# Shield_DMM.net
KiCad netlist of a schematic drawn in EAGLE
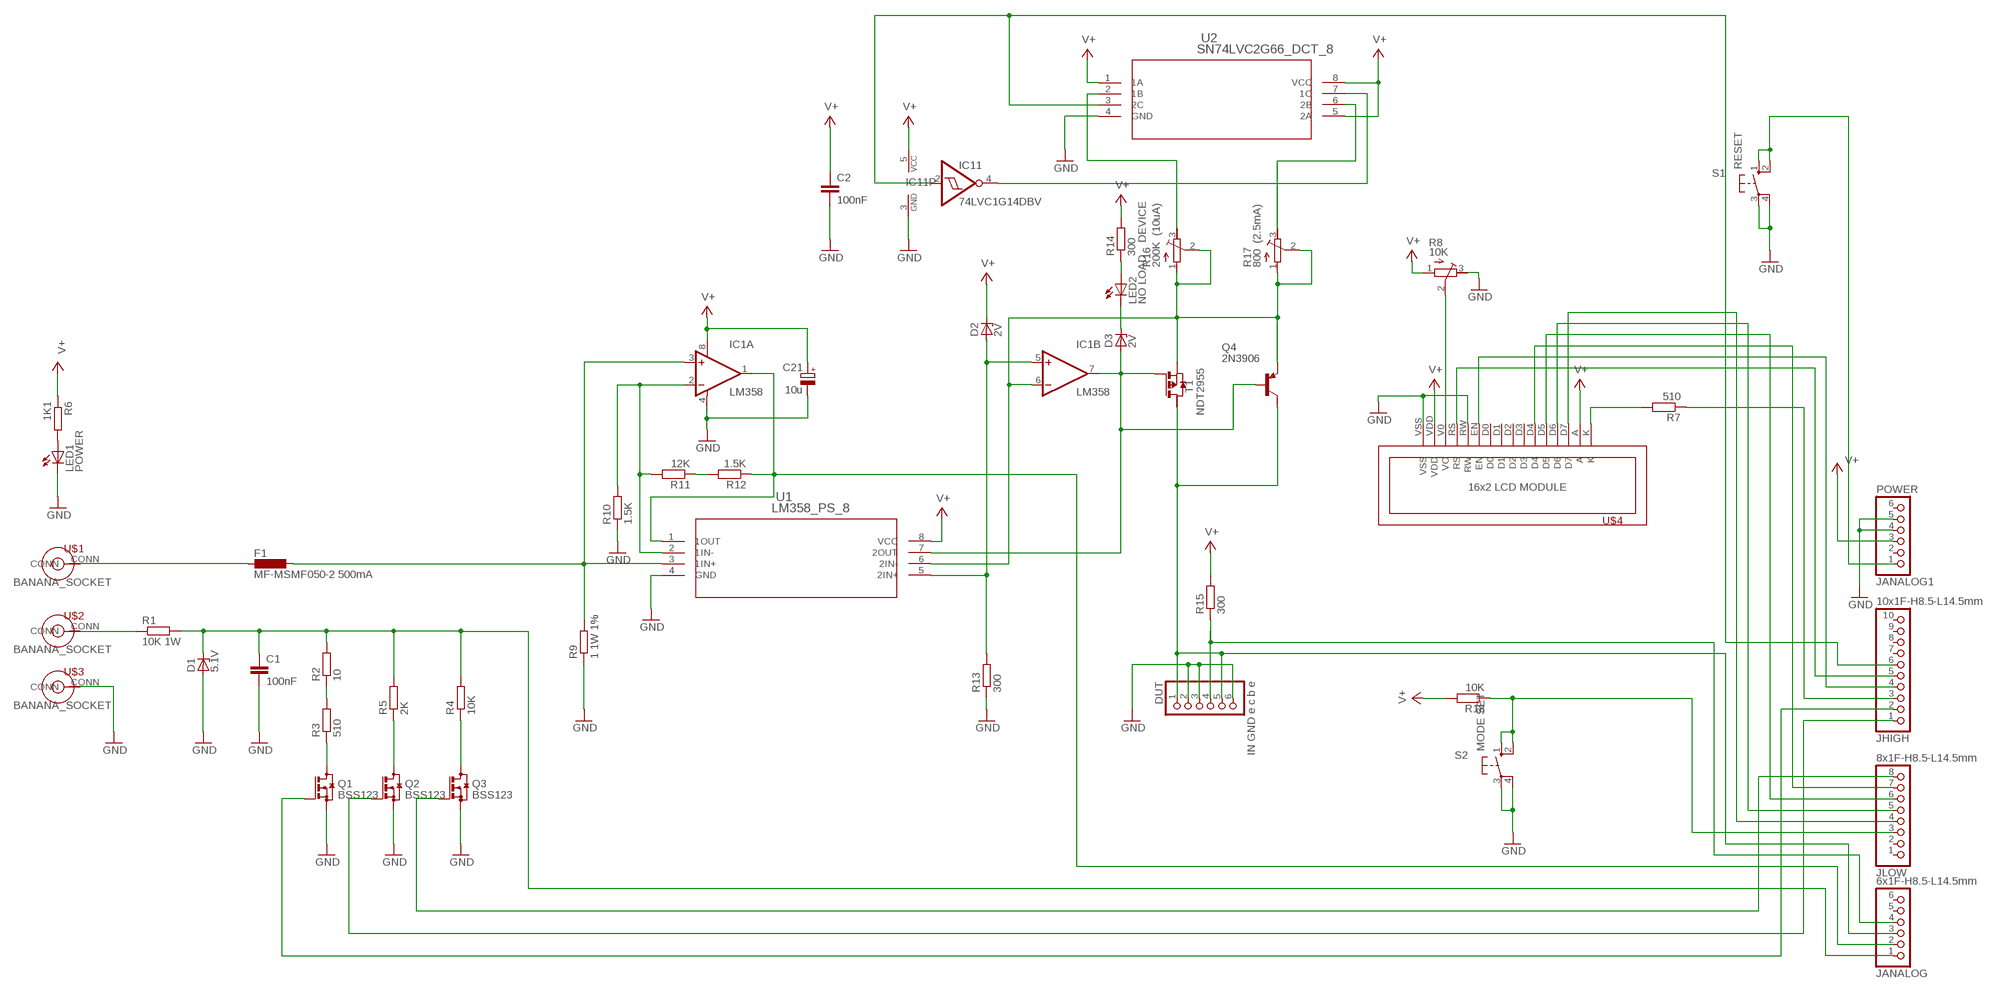
[diagram p0: schematic, sheet 1]

(export (version "E")
  (design (tool "Eeschema 10.0.6"))
  (components
    (comp (ref "C1")
      (value "100nF")
      (footprint "eagle-import:C0805")
      (libsource (lib "eagle-import") (part "C-EUC0805"))
    )
    (comp (ref "C2")
      (value "100nF")
      (footprint "eagle-import:C0805")
      (libsource (lib "eagle-import") (part "C-EUC0805"))
    )
    (comp (ref "C21")
      (value "10u")
      (footprint "eagle-import:085CS_1AR")
      (libsource (lib "eagle-import") (part "CPOL-EU085CS-1AR"))
    )
    (comp (ref "D1")
      (value "5.1V")
      (footprint "eagle-import:DO34Z7")
      (libsource (lib "eagle-import") (part "BZV10"))
    )
    (comp (ref "D2")
      (value "2V")
      (footprint "eagle-import:DO34Z7")
      (libsource (lib "eagle-import") (part "BZV10"))
    )
    (comp (ref "D3")
      (value "2V")
      (footprint "eagle-import:DO34Z7")
      (libsource (lib "eagle-import") (part "BZV10"))
    )
    (comp (ref "DUT")
      (value "IN GND e c b e")
      (footprint "eagle-import:1X06")
      (libsource (lib "eagle-import") (part "PINHD-1X6"))
    )
    (comp (ref "F1")
      (value "MF-MSMF050-2 500mA")
      (footprint "eagle-import:L1812")
      (libsource (lib "eagle-import") (part "L-EUL1812"))
    )
    (comp (ref "IC1")
      (value "LM358")
      (footprint "eagle-import:SO08")
      (fields (field (name "MF") "TEXAS INSTRUMENTS") (field (name "MPN") "OPA2340UA"))
      (libsource (lib "eagle-import") (part "OPA2340U"))
    )
    (comp (ref "IC11")
      (value "74LVC1G14DBV")
      (footprint "eagle-import:SOT23-5")
      (libsource (lib "eagle-import") (part "741G14DBVLVC"))
    )
    (comp (ref "JANALOG")
      (value "6x1F-H8.5-L14.5mm")
      (footprint "eagle-import:1X06")
      (libsource (lib "eagle-import") (part "PINHD-1X6"))
    )
    (comp (ref "JANALOG1")
      (value "POWER")
      (footprint "eagle-import:1X06")
      (libsource (lib "eagle-import") (part "PINHD-1X6"))
    )
    (comp (ref "JHIGH")
      (value "10x1F-H8.5-L14.5mm")
      (footprint "eagle-import:1X10")
      (libsource (lib "eagle-import") (part "PINHD-1X10"))
    )
    (comp (ref "JLOW")
      (value "8x1F-H8.5-L14.5mm")
      (footprint "eagle-import:1X08")
      (libsource (lib "eagle-import") (part "PINHD-1X8"))
    )
    (comp (ref "LED1")
      (value "POWER")
      (footprint "eagle-import:CHIPLED_0805")
      (libsource (lib "eagle-import") (part "LEDCHIPLED_0805"))
    )
    (comp (ref "LED2")
      (value "NO LOAD DEVICE")
      (footprint "eagle-import:CHIPLED_0805")
      (libsource (lib "eagle-import") (part "LEDCHIPLED_0805"))
    )
    (comp (ref "Q1")
      (value "BSS123")
      (footprint "eagle-import:SOT23")
      (libsource (lib "eagle-import") (part "BSS123"))
    )
    (comp (ref "Q2")
      (value "BSS123")
      (footprint "eagle-import:SOT23")
      (libsource (lib "eagle-import") (part "BSS123"))
    )
    (comp (ref "Q3")
      (value "BSS123")
      (footprint "eagle-import:SOT23")
      (libsource (lib "eagle-import") (part "BSS123"))
    )
    (comp (ref "Q4")
      (value "2N3906")
      (footprint "eagle-import:TO92")
      (libsource (lib "eagle-import") (part "2N3906"))
    )
    (comp (ref "R1")
      (value "10K 1W")
      (footprint "eagle-import:0207_10")
      (libsource (lib "eagle-import") (part "R-EU_0207/10"))
    )
    (comp (ref "R2")
      (value "10")
      (footprint "eagle-import:R0805")
      (libsource (lib "eagle-import") (part "R-EU_R0805"))
    )
    (comp (ref "R3")
      (value "510")
      (footprint "eagle-import:R0805")
      (libsource (lib "eagle-import") (part "R-EU_R0805"))
    )
    (comp (ref "R4")
      (value "10K")
      (footprint "eagle-import:R0805")
      (libsource (lib "eagle-import") (part "R-EU_R0805"))
    )
    (comp (ref "R5")
      (value "2K")
      (footprint "eagle-import:R0805")
      (libsource (lib "eagle-import") (part "R-EU_R0805"))
    )
    (comp (ref "R6")
      (value "1K1")
      (footprint "eagle-import:R0805")
      (libsource (lib "eagle-import") (part "R-EU_R0805"))
    )
    (comp (ref "R7")
      (value "510")
      (footprint "eagle-import:R0805")
      (libsource (lib "eagle-import") (part "R-EU_R0805"))
    )
    (comp (ref "R8")
      (value "10K")
      (footprint "eagle-import:RTRIM64W")
      (libsource (lib "eagle-import") (part "R-TRIMM64W"))
    )
    (comp (ref "R9")
      (value "1 1W 1%")
      (footprint "eagle-import:0207_10")
      (libsource (lib "eagle-import") (part "R-EU_0207/10"))
    )
    (comp (ref "R10")
      (value "1.5K")
      (footprint "eagle-import:R0805")
      (libsource (lib "eagle-import") (part "R-EU_R0805"))
    )
    (comp (ref "R11")
      (value "12K")
      (footprint "eagle-import:R0805")
      (libsource (lib "eagle-import") (part "R-EU_R0805"))
    )
    (comp (ref "R12")
      (value "1.5K")
      (footprint "eagle-import:R0805")
      (libsource (lib "eagle-import") (part "R-EU_R0805"))
    )
    (comp (ref "R13")
      (value "300")
      (footprint "eagle-import:R0805")
      (libsource (lib "eagle-import") (part "R-EU_R0805"))
    )
    (comp (ref "R14")
      (value "300")
      (footprint "eagle-import:R0805")
      (libsource (lib "eagle-import") (part "R-EU_R0805"))
    )
    (comp (ref "R15")
      (value "300")
      (footprint "eagle-import:R0805")
      (libsource (lib "eagle-import") (part "R-EU_R0805"))
    )
    (comp (ref "R16")
      (value "200K (10uA)")
      (footprint "eagle-import:RTRIM64W")
      (libsource (lib "eagle-import") (part "R-TRIMM64W"))
    )
    (comp (ref "R17")
      (value "800 (2.5mA)")
      (footprint "eagle-import:RTRIM64W")
      (libsource (lib "eagle-import") (part "R-TRIMM64W"))
    )
    (comp (ref "R18")
      (value "10K")
      (footprint "eagle-import:R0805")
      (libsource (lib "eagle-import") (part "R-EU_R0805"))
    )
    (comp (ref "S1")
      (value "RESET")
      (footprint "eagle-import:B3F-10XX")
      (libsource (lib "eagle-import") (part "10-XX"))
    )
    (comp (ref "S2")
      (value "MODE SET")
      (footprint "eagle-import:B3F-10XX")
      (libsource (lib "eagle-import") (part "10-XX"))
    )
    (comp (ref "T1")
      (value "NDT2955")
      (footprint "eagle-import:SOT223")
      (libsource (lib "eagle-import") (part "PMOSSOT223"))
    )
    (comp (ref "U$1")
      (value "BANANA_CONN")
      (footprint "eagle-import:BANANA_CONN")
      (libsource (lib "eagle-import") (part "BANANA_CONN"))
    )
    (comp (ref "U$2")
      (value "BANANA_CONN")
      (footprint "eagle-import:BANANA_CONN")
      (libsource (lib "eagle-import") (part "BANANA_CONN"))
    )
    (comp (ref "U$3")
      (value "BANANA_CONN")
      (footprint "eagle-import:BANANA_CONN")
      (libsource (lib "eagle-import") (part "BANANA_CONN"))
    )
    (comp (ref "U$4")
      (value "1602_LCM")
      (footprint "eagle-import:1602_LCM")
      (libsource (lib "eagle-import") (part "1602_LCM"))
    )
    (comp (ref "U1")
      (value "LM358_PS_8")
      (footprint "eagle-import:PS8")
      (fields (field (name "GENERIC_PART_NUMBER") "LM358") (field (name "MANUFACTURER") "Texas Instruments"))
      (libsource (lib "eagle-import") (part "LM358_PS_8"))
    )
    (comp (ref "U2")
      (value "SN74LVC2G66_DCT_8")
      (footprint "eagle-import:DCT8")
      (fields
        (field (name "GENERIC_PART_NUMBER") "SN74LVC2G66")
        (field (name "MANUFACTURER") "Texas Instruments")
        (field (name "MANUFACTURER_PART_NUMBER") "sn74lvc2g66_dct_8")
      )
      (libsource (lib "eagle-import") (part "SN74LVC2G66_DCT_8"))
    )
  )
  (nets
    (net (code "1") (name "GND") (class "Default")
      (node (ref "C1") (pin "2") (pinfunction "2_2") (pintype "passive"))
      (node (ref "C2") (pin "2") (pinfunction "2_2") (pintype "passive"))
      (node (ref "C21") (pin "-") (pinfunction "-_-") (pintype "passive"))
      (node (ref "D1") (pin "A") (pinfunction "A_A") (pintype "passive"))
      (node (ref "DUT") (pin "2") (pinfunction "2_2") (pintype "passive"))
      (node (ref "DUT") (pin "3") (pinfunction "3_3") (pintype "passive"))
      (node (ref "DUT") (pin "6") (pinfunction "6_6") (pintype "passive"))
      (node (ref "IC1") (pin "4") (pinfunction "V-_4") (pintype "power_in"))
      (node (ref "IC11") (pin "3") (pinfunction "GND_3") (pintype "power_in"))
      (node (ref "JANALOG1") (pin "4") (pinfunction "4_4") (pintype "passive"))
      (node (ref "JANALOG1") (pin "5") (pinfunction "5_5") (pintype "passive"))
      (node (ref "LED1") (pin "C") (pinfunction "C_C") (pintype "passive"))
      (node (ref "Q1") (pin "2") (pinfunction "S_2") (pintype "passive"))
      (node (ref "Q2") (pin "2") (pinfunction "S_2") (pintype "passive"))
      (node (ref "Q3") (pin "2") (pinfunction "S_2") (pintype "passive"))
      (node (ref "R10") (pin "1") (pinfunction "1_1") (pintype "passive"))
      (node (ref "R13") (pin "1") (pinfunction "1_1") (pintype "passive"))
      (node (ref "R8") (pin "3") (pinfunction "E_3") (pintype "passive"))
      (node (ref "R9") (pin "1") (pinfunction "1_1") (pintype "passive"))
      (node (ref "S1") (pin "3") (pinfunction "P_3") (pintype "passive"))
      (node (ref "S1") (pin "4") (pinfunction "P1_4") (pintype "passive"))
      (node (ref "S2") (pin "3") (pinfunction "P_3") (pintype "passive"))
      (node (ref "S2") (pin "4") (pinfunction "P1_4") (pintype "passive"))
      (node (ref "U$3") (pin "CONN") (pinfunction "CONN_CONN") (pintype "bidirectional"))
      (node (ref "U$4") (pin "RW") (pinfunction "RW_RW") (pintype "bidirectional"))
      (node (ref "U$4") (pin "VSS") (pinfunction "VSS_VSS") (pintype "bidirectional"))
      (node (ref "U1") (pin "4") (pinfunction "GND_4") (pintype "power_in"))
      (node (ref "U2") (pin "4") (pinfunction "GND_4") (pintype "power_in"))
    )
    (net (code "2") (name "Net-(C1-Pad1)") (class "Default")
      (node (ref "C1") (pin "1") (pinfunction "1_1") (pintype "passive"))
      (node (ref "D1") (pin "C") (pinfunction "C_C") (pintype "passive"))
      (node (ref "JANALOG") (pin "1") (pinfunction "1_1") (pintype "passive"))
      (node (ref "R1") (pin "2") (pinfunction "2_2") (pintype "passive"))
      (node (ref "R2") (pin "2") (pinfunction "2_2") (pintype "passive"))
      (node (ref "R4") (pin "2") (pinfunction "2_2") (pintype "passive"))
      (node (ref "R5") (pin "2") (pinfunction "2_2") (pintype "passive"))
    )
    (net (code "3") (name "Net-(D3-PadC)") (class "Default")
      (node (ref "D3") (pin "C") (pinfunction "C_C") (pintype "passive"))
      (node (ref "LED2") (pin "C") (pinfunction "C_C") (pintype "passive"))
    )
    (net (code "4") (name "Net-(DUT-Pad4)") (class "Default")
      (node (ref "DUT") (pin "4") (pinfunction "4_4") (pintype "passive"))
      (node (ref "JANALOG") (pin "4") (pinfunction "4_4") (pintype "passive"))
      (node (ref "R15") (pin "1") (pinfunction "1_1") (pintype "passive"))
    )
    (net (code "5") (name "Net-(F1-Pad2)") (class "Default")
      (node (ref "F1") (pin "2") (pinfunction "2_2") (pintype "passive"))
      (node (ref "U$1") (pin "CONN") (pinfunction "CONN_CONN") (pintype "bidirectional"))
    )
    (net (code "6") (name "Net-(IC1A-+IN)") (class "Default")
      (node (ref "F1") (pin "1") (pinfunction "1_1") (pintype "passive"))
      (node (ref "IC1") (pin "3") (pinfunction "+IN_3") (pintype "input"))
      (node (ref "R9") (pin "2") (pinfunction "2_2") (pintype "passive"))
      (node (ref "U1") (pin "3") (pinfunction "1IN+_3") (pintype "input"))
    )
    (net (code "7") (name "Net-(IC1A--IN)") (class "Default")
      (node (ref "IC1") (pin "2") (pinfunction "-IN_2") (pintype "input"))
      (node (ref "R10") (pin "2") (pinfunction "2_2") (pintype "passive"))
      (node (ref "R11") (pin "2") (pinfunction "2_2") (pintype "passive"))
      (node (ref "U1") (pin "2") (pinfunction "1IN-_2") (pintype "input"))
    )
    (net (code "8") (name "Net-(IC1A-OUT)") (class "Default")
      (node (ref "IC1") (pin "1") (pinfunction "OUT_1") (pintype "output"))
      (node (ref "JANALOG") (pin "2") (pinfunction "2_2") (pintype "passive"))
      (node (ref "R12") (pin "1") (pinfunction "1_1") (pintype "passive"))
      (node (ref "U1") (pin "1") (pinfunction "1OUT_1") (pintype "output"))
    )
    (net (code "9") (name "Net-(IC1B-+IN)") (class "Default")
      (node (ref "D2") (pin "A") (pinfunction "A_A") (pintype "passive"))
      (node (ref "IC1") (pin "5") (pinfunction "+IN_5") (pintype "input"))
      (node (ref "R13") (pin "2") (pinfunction "2_2") (pintype "passive"))
      (node (ref "U1") (pin "5") (pinfunction "2IN+_5") (pintype "input"))
    )
    (net (code "10") (name "Net-(IC1B--IN)") (class "Default")
      (node (ref "IC1") (pin "6") (pinfunction "-IN_6") (pintype "input"))
      (node (ref "Q4") (pin "3") (pinfunction "E_3") (pintype "passive"))
      (node (ref "R16") (pin "1") (pinfunction "A_1") (pintype "passive"))
      (node (ref "R16") (pin "2") (pinfunction "S_2") (pintype "passive"))
      (node (ref "R17") (pin "1") (pinfunction "A_1") (pintype "passive"))
      (node (ref "R17") (pin "2") (pinfunction "S_2") (pintype "passive"))
      (node (ref "T1") (pin "3") (pinfunction "S_3") (pintype "passive"))
      (node (ref "U1") (pin "6") (pinfunction "2IN-_6") (pintype "input"))
    )
    (net (code "11") (name "Net-(IC1B-OUT)") (class "Default")
      (node (ref "D3") (pin "A") (pinfunction "A_A") (pintype "passive"))
      (node (ref "IC1") (pin "7") (pinfunction "OUT_7") (pintype "output"))
      (node (ref "Q4") (pin "2") (pinfunction "B_2") (pintype "passive"))
      (node (ref "T1") (pin "1") (pinfunction "G_1") (pintype "passive"))
      (node (ref "U1") (pin "7") (pinfunction "2OUT_7") (pintype "output"))
    )
    (net (code "12") (name "Net-(IC11A-I)") (class "Default")
      (node (ref "IC11") (pin "2") (pinfunction "I_2") (pintype "input"))
      (node (ref "JHIGH") (pin "6") (pinfunction "6_6") (pintype "passive"))
      (node (ref "U2") (pin "3") (pinfunction "2C_3") (pintype "input"))
    )
    (net (code "13") (name "Net-(IC11A-O)") (class "Default")
      (node (ref "IC11") (pin "4") (pinfunction "O_4") (pintype "output"))
      (node (ref "U2") (pin "7") (pinfunction "1C_7") (pintype "input"))
    )
    (net (code "14") (name "Net-(JHIGH-Pad3)") (class "Default")
      (node (ref "JHIGH") (pin "3") (pinfunction "3_3") (pintype "passive"))
      (node (ref "R7") (pin "1") (pinfunction "1_1") (pintype "passive"))
    )
    (net (code "15") (name "Net-(JHIGH-Pad4)") (class "Default")
      (node (ref "JHIGH") (pin "4") (pinfunction "4_4") (pintype "passive"))
      (node (ref "U$4") (pin "EN") (pinfunction "EN_EN") (pintype "bidirectional"))
    )
    (net (code "16") (name "Net-(JHIGH-Pad5)") (class "Default")
      (node (ref "JHIGH") (pin "5") (pinfunction "5_5") (pintype "passive"))
      (node (ref "U$4") (pin "RS") (pinfunction "RS_RS") (pintype "bidirectional"))
    )
    (net (code "17") (name "Net-(JLOW-Pad4)") (class "Default")
      (node (ref "JLOW") (pin "4") (pinfunction "4_4") (pintype "passive"))
      (node (ref "U$4") (pin "D7") (pinfunction "D7_D7") (pintype "bidirectional"))
    )
    (net (code "18") (name "Net-(JLOW-Pad5)") (class "Default")
      (node (ref "JLOW") (pin "5") (pinfunction "5_5") (pintype "passive"))
      (node (ref "U$4") (pin "D6") (pinfunction "D6_D6") (pintype "bidirectional"))
    )
    (net (code "19") (name "Net-(JLOW-Pad6)") (class "Default")
      (node (ref "JLOW") (pin "6") (pinfunction "6_6") (pintype "passive"))
      (node (ref "U$4") (pin "D5") (pinfunction "D5_D5") (pintype "bidirectional"))
    )
    (net (code "20") (name "Net-(JLOW-Pad7)") (class "Default")
      (node (ref "JLOW") (pin "7") (pinfunction "7_7") (pintype "passive"))
      (node (ref "U$4") (pin "D4") (pinfunction "D4_D4") (pintype "bidirectional"))
    )
    (net (code "21") (name "Net-(LED1-PadA)") (class "Default")
      (node (ref "LED1") (pin "A") (pinfunction "A_A") (pintype "passive"))
      (node (ref "R6") (pin "2") (pinfunction "2_2") (pintype "passive"))
    )
    (net (code "22") (name "Net-(LED2-PadA)") (class "Default")
      (node (ref "LED2") (pin "A") (pinfunction "A_A") (pintype "passive"))
      (node (ref "R14") (pin "1") (pinfunction "1_1") (pintype "passive"))
    )
    (net (code "23") (name "Net-(Q1-D)") (class "Default")
      (node (ref "Q1") (pin "3") (pinfunction "D_3") (pintype "passive"))
      (node (ref "R3") (pin "1") (pinfunction "1_1") (pintype "passive"))
    )
    (net (code "24") (name "Net-(Q1-G)") (class "Default")
      (node (ref "JHIGH") (pin "2") (pinfunction "2_2") (pintype "passive"))
      (node (ref "Q1") (pin "1") (pinfunction "G_1") (pintype "passive"))
    )
    (net (code "25") (name "Net-(Q2-D)") (class "Default")
      (node (ref "Q2") (pin "3") (pinfunction "D_3") (pintype "passive"))
      (node (ref "R5") (pin "1") (pinfunction "1_1") (pintype "passive"))
    )
    (net (code "26") (name "Net-(Q2-G)") (class "Default")
      (node (ref "JHIGH") (pin "1") (pinfunction "1_1") (pintype "passive"))
      (node (ref "Q2") (pin "1") (pinfunction "G_1") (pintype "passive"))
    )
    (net (code "27") (name "Net-(Q3-D)") (class "Default")
      (node (ref "Q3") (pin "3") (pinfunction "D_3") (pintype "passive"))
      (node (ref "R4") (pin "1") (pinfunction "1_1") (pintype "passive"))
    )
    (net (code "28") (name "Net-(Q3-G)") (class "Default")
      (node (ref "JLOW") (pin "8") (pinfunction "8_8") (pintype "passive"))
      (node (ref "Q3") (pin "1") (pinfunction "G_1") (pintype "passive"))
    )
    (net (code "29") (name "Net-(Q4-C)") (class "Default")
      (node (ref "DUT") (pin "1") (pinfunction "1_1") (pintype "passive"))
      (node (ref "DUT") (pin "5") (pinfunction "5_5") (pintype "passive"))
      (node (ref "JANALOG") (pin "3") (pinfunction "3_3") (pintype "passive"))
      (node (ref "Q4") (pin "1") (pinfunction "C_1") (pintype "passive"))
      (node (ref "T1") (pin "2") (pinfunction "D_2") (pintype "passive"))
    )
    (net (code "30") (name "Net-(R1-Pad1)") (class "Default")
      (node (ref "R1") (pin "1") (pinfunction "1_1") (pintype "passive"))
      (node (ref "U$2") (pin "CONN") (pinfunction "CONN_CONN") (pintype "bidirectional"))
    )
    (net (code "31") (name "Net-(R2-Pad1)") (class "Default")
      (node (ref "R2") (pin "1") (pinfunction "1_1") (pintype "passive"))
      (node (ref "R3") (pin "2") (pinfunction "2_2") (pintype "passive"))
    )
    (net (code "32") (name "Net-(R7-Pad2)") (class "Default")
      (node (ref "R7") (pin "2") (pinfunction "2_2") (pintype "passive"))
      (node (ref "U$4") (pin "K") (pinfunction "K_K") (pintype "bidirectional"))
    )
    (net (code "33") (name "Net-(R8-S)") (class "Default")
      (node (ref "R8") (pin "2") (pinfunction "S_2") (pintype "passive"))
      (node (ref "U$4") (pin "V0") (pinfunction "VO_V0") (pintype "bidirectional"))
    )
    (net (code "34") (name "Net-(R11-Pad1)") (class "Default")
      (node (ref "R11") (pin "1") (pinfunction "1_1") (pintype "passive"))
      (node (ref "R12") (pin "2") (pinfunction "2_2") (pintype "passive"))
    )
    (net (code "35") (name "Net-(R16-E)") (class "Default")
      (node (ref "R16") (pin "3") (pinfunction "E_3") (pintype "passive"))
      (node (ref "U2") (pin "2") (pinfunction "1B_2") (pintype "input"))
    )
    (net (code "36") (name "Net-(R17-E)") (class "Default")
      (node (ref "R17") (pin "3") (pinfunction "E_3") (pintype "passive"))
      (node (ref "U2") (pin "6") (pinfunction "2B_6") (pintype "input"))
    )
    (net (code "37") (name "Net-(S1-S)") (class "Default")
      (node (ref "JANALOG1") (pin "1") (pinfunction "1_1") (pintype "passive"))
      (node (ref "S1") (pin "1") (pinfunction "S_1") (pintype "passive"))
      (node (ref "S1") (pin "2") (pinfunction "S1_2") (pintype "passive"))
    )
    (net (code "38") (name "Net-(S2-S)") (class "Default")
      (node (ref "JLOW") (pin "3") (pinfunction "3_3") (pintype "passive"))
      (node (ref "R18") (pin "1") (pinfunction "1_1") (pintype "passive"))
      (node (ref "S2") (pin "1") (pinfunction "S_1") (pintype "passive"))
      (node (ref "S2") (pin "2") (pinfunction "S1_2") (pintype "passive"))
    )
    (net (code "39") (name "V+") (class "Default")
      (node (ref "C2") (pin "1") (pinfunction "1_1") (pintype "passive"))
      (node (ref "C21") (pin "+") (pinfunction "+_+") (pintype "passive"))
      (node (ref "D2") (pin "C") (pinfunction "C_C") (pintype "passive"))
      (node (ref "IC1") (pin "8") (pinfunction "V+_8") (pintype "power_in"))
      (node (ref "IC11") (pin "5") (pinfunction "VCC_5") (pintype "power_in"))
      (node (ref "JANALOG1") (pin "3") (pinfunction "3_3") (pintype "passive"))
      (node (ref "R14") (pin "2") (pinfunction "2_2") (pintype "passive"))
      (node (ref "R15") (pin "2") (pinfunction "2_2") (pintype "passive"))
      (node (ref "R18") (pin "2") (pinfunction "2_2") (pintype "passive"))
      (node (ref "R6") (pin "1") (pinfunction "1_1") (pintype "passive"))
      (node (ref "R8") (pin "1") (pinfunction "A_1") (pintype "passive"))
      (node (ref "U$4") (pin "A") (pinfunction "A_A") (pintype "bidirectional"))
      (node (ref "U$4") (pin "VDD") (pinfunction "VDD_VDD") (pintype "bidirectional"))
      (node (ref "U1") (pin "8") (pinfunction "VCC_8") (pintype "power_in"))
      (node (ref "U2") (pin "1") (pinfunction "1A_1") (pintype "input"))
      (node (ref "U2") (pin "5") (pinfunction "2A_5") (pintype "input"))
      (node (ref "U2") (pin "8") (pinfunction "VCC_8") (pintype "power_in"))
    )
    (net (code "40") (name "unconnected-(JANALOG-Pad5)") (class "Default")
      (node (ref "JANALOG") (pin "5") (pinfunction "5_5") (pintype "passive"))
    )
    (net (code "41") (name "unconnected-(JANALOG-Pad6)") (class "Default")
      (node (ref "JANALOG") (pin "6") (pinfunction "6_6") (pintype "passive"))
    )
    (net (code "42") (name "unconnected-(JANALOG1-Pad2)") (class "Default")
      (node (ref "JANALOG1") (pin "2") (pinfunction "2_2") (pintype "passive"))
    )
    (net (code "43") (name "unconnected-(JANALOG1-Pad6)") (class "Default")
      (node (ref "JANALOG1") (pin "6") (pinfunction "6_6") (pintype "passive"))
    )
    (net (code "44") (name "unconnected-(JHIGH-Pad7)") (class "Default")
      (node (ref "JHIGH") (pin "7") (pinfunction "7_7") (pintype "passive"))
    )
    (net (code "45") (name "unconnected-(JHIGH-Pad8)") (class "Default")
      (node (ref "JHIGH") (pin "8") (pinfunction "8_8") (pintype "passive"))
    )
    (net (code "46") (name "unconnected-(JHIGH-Pad9)") (class "Default")
      (node (ref "JHIGH") (pin "9") (pinfunction "9_9") (pintype "passive"))
    )
    (net (code "47") (name "unconnected-(JHIGH-Pad10)") (class "Default")
      (node (ref "JHIGH") (pin "10") (pinfunction "10_10") (pintype "passive"))
    )
    (net (code "48") (name "unconnected-(JLOW-Pad1)") (class "Default")
      (node (ref "JLOW") (pin "1") (pinfunction "1_1") (pintype "passive"))
    )
    (net (code "49") (name "unconnected-(JLOW-Pad2)") (class "Default")
      (node (ref "JLOW") (pin "2") (pinfunction "2_2") (pintype "passive"))
    )
    (net (code "50") (name "unconnected-(T1-D2-Pad4)") (class "Default")
      (node (ref "T1") (pin "4") (pinfunction "D2_4") (pintype "passive"))
    )
    (net (code "51") (name "unconnected-(U$4-PadD0)") (class "Default")
      (node (ref "U$4") (pin "D0") (pinfunction "D0_D0") (pintype "bidirectional"))
    )
    (net (code "52") (name "unconnected-(U$4-PadD1)") (class "Default")
      (node (ref "U$4") (pin "D1") (pinfunction "D1_D1") (pintype "bidirectional"))
    )
    (net (code "53") (name "unconnected-(U$4-PadD2)") (class "Default")
      (node (ref "U$4") (pin "D2") (pinfunction "D2_D2") (pintype "bidirectional"))
    )
    (net (code "54") (name "unconnected-(U$4-PadD3)") (class "Default")
      (node (ref "U$4") (pin "D3") (pinfunction "D3_D3") (pintype "bidirectional"))
    )
  )
)
